# module_RF69.net
KiCad netlist of a schematic drawn in EAGLE
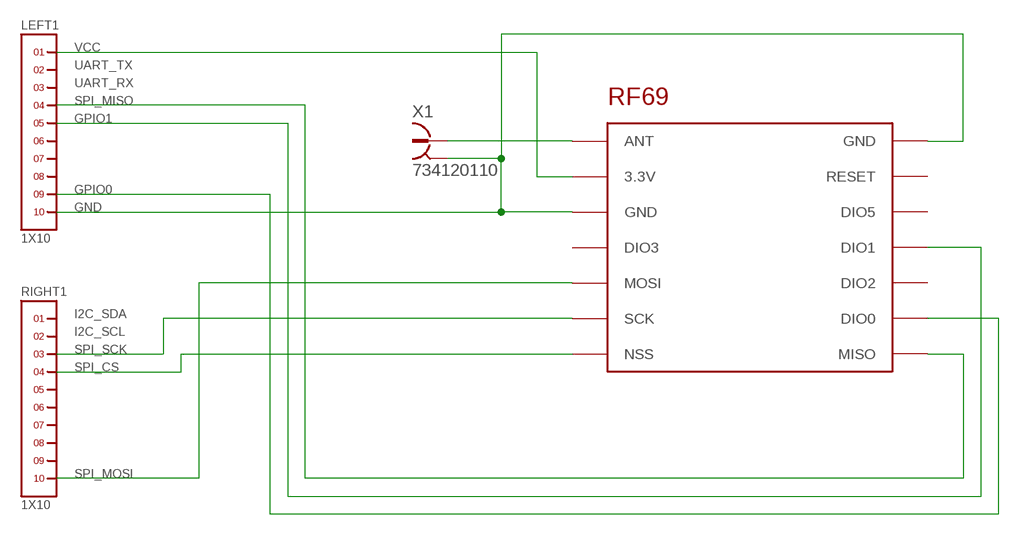
[diagram p0: schematic, sheet 1]

(export (version "E")
  (design (tool "Eeschema 10.0.6"))
  (components
    (comp (ref "LEFT1")
      (value "1X10")
      (footprint "eagle-import:1X10")
      (libsource (lib "eagle-import") (part "1X10"))
    )
    (comp (ref "RIGHT1")
      (value "1X10")
      (footprint "eagle-import:1X10")
      (libsource (lib "eagle-import") (part "1X10"))
    )
    (comp (ref "U$1")
      (value "RF69")
      (footprint "eagle-import:RF69")
      (libsource (lib "eagle-import") (part "RF69"))
    )
    (comp (ref "X1")
      (value "734120110")
      (footprint "eagle-import:734120110")
      (libsource (lib "eagle-import") (part "734120110"))
    )
  )
  (nets
    (net (code "1") (name "Net-(LEFT1-Pad1)") (class "Default")
      (node (ref "LEFT1") (pin "1") (pinfunction "1_1") (pintype "bidirectional"))
      (node (ref "U$1") (pin "3.3V") (pinfunction "3.3V_3.3V") (pintype "bidirectional"))
    )
    (net (code "2") (name "Net-(LEFT1-Pad4)") (class "Default")
      (node (ref "LEFT1") (pin "4") (pinfunction "4_4") (pintype "bidirectional"))
      (node (ref "U$1") (pin "MISO") (pinfunction "MISO_MISO") (pintype "bidirectional"))
    )
    (net (code "3") (name "Net-(LEFT1-Pad5)") (class "Default")
      (node (ref "LEFT1") (pin "5") (pinfunction "5_5") (pintype "bidirectional"))
      (node (ref "U$1") (pin "DIO1") (pinfunction "DIO1_DIO1") (pintype "bidirectional"))
    )
    (net (code "4") (name "Net-(LEFT1-Pad9)") (class "Default")
      (node (ref "LEFT1") (pin "9") (pinfunction "9_9") (pintype "bidirectional"))
      (node (ref "U$1") (pin "DIO0") (pinfunction "DIO0_DIO0") (pintype "bidirectional"))
    )
    (net (code "5") (name "Net-(LEFT1-Pad10)") (class "Default")
      (node (ref "LEFT1") (pin "10") (pinfunction "10_10") (pintype "bidirectional"))
      (node (ref "U$1") (pin "GND@1") (pinfunction "GND_GND@1") (pintype "bidirectional"))
      (node (ref "U$1") (pin "GND@2") (pinfunction "GND_GND@2") (pintype "bidirectional"))
      (node (ref "X1") (pin "S@1") (pinfunction "2_S@1") (pintype "passive"))
      (node (ref "X1") (pin "S@2") (pinfunction "2_S@2") (pintype "passive"))
      (node (ref "X1") (pin "S@3") (pinfunction "2_S@3") (pintype "passive"))
    )
    (net (code "6") (name "Net-(RIGHT1-Pad3)") (class "Default")
      (node (ref "RIGHT1") (pin "3") (pinfunction "3_3") (pintype "bidirectional"))
      (node (ref "U$1") (pin "SCK") (pinfunction "SCK_SCK") (pintype "bidirectional"))
    )
    (net (code "7") (name "Net-(RIGHT1-Pad4)") (class "Default")
      (node (ref "RIGHT1") (pin "4") (pinfunction "4_4") (pintype "bidirectional"))
      (node (ref "U$1") (pin "NSS") (pinfunction "NSS_NSS") (pintype "bidirectional"))
    )
    (net (code "8") (name "Net-(RIGHT1-Pad10)") (class "Default")
      (node (ref "RIGHT1") (pin "10") (pinfunction "10_10") (pintype "bidirectional"))
      (node (ref "U$1") (pin "MOSI") (pinfunction "MOSI_MOSI") (pintype "bidirectional"))
    )
    (net (code "9") (name "Net-(U$1-PadANT)") (class "Default")
      (node (ref "U$1") (pin "ANT") (pinfunction "ANT_ANT") (pintype "bidirectional"))
      (node (ref "X1") (pin "1") (pinfunction "1_1") (pintype "passive"))
    )
    (net (code "10") (name "unconnected-(LEFT1-Pad2)") (class "Default")
      (node (ref "LEFT1") (pin "2") (pinfunction "2_2") (pintype "bidirectional"))
    )
    (net (code "11") (name "unconnected-(LEFT1-Pad3)") (class "Default")
      (node (ref "LEFT1") (pin "3") (pinfunction "3_3") (pintype "bidirectional"))
    )
    (net (code "12") (name "unconnected-(LEFT1-Pad6)") (class "Default")
      (node (ref "LEFT1") (pin "6") (pinfunction "6_6") (pintype "bidirectional"))
    )
    (net (code "13") (name "unconnected-(LEFT1-Pad7)") (class "Default")
      (node (ref "LEFT1") (pin "7") (pinfunction "7_7") (pintype "bidirectional"))
    )
    (net (code "14") (name "unconnected-(LEFT1-Pad8)") (class "Default")
      (node (ref "LEFT1") (pin "8") (pinfunction "8_8") (pintype "bidirectional"))
    )
    (net (code "15") (name "unconnected-(RIGHT1-Pad1)") (class "Default")
      (node (ref "RIGHT1") (pin "1") (pinfunction "1_1") (pintype "bidirectional"))
    )
    (net (code "16") (name "unconnected-(RIGHT1-Pad2)") (class "Default")
      (node (ref "RIGHT1") (pin "2") (pinfunction "2_2") (pintype "bidirectional"))
    )
    (net (code "17") (name "unconnected-(RIGHT1-Pad5)") (class "Default")
      (node (ref "RIGHT1") (pin "5") (pinfunction "5_5") (pintype "bidirectional"))
    )
    (net (code "18") (name "unconnected-(RIGHT1-Pad6)") (class "Default")
      (node (ref "RIGHT1") (pin "6") (pinfunction "6_6") (pintype "bidirectional"))
    )
    (net (code "19") (name "unconnected-(RIGHT1-Pad7)") (class "Default")
      (node (ref "RIGHT1") (pin "7") (pinfunction "7_7") (pintype "bidirectional"))
    )
    (net (code "20") (name "unconnected-(RIGHT1-Pad8)") (class "Default")
      (node (ref "RIGHT1") (pin "8") (pinfunction "8_8") (pintype "bidirectional"))
    )
    (net (code "21") (name "unconnected-(RIGHT1-Pad9)") (class "Default")
      (node (ref "RIGHT1") (pin "9") (pinfunction "9_9") (pintype "bidirectional"))
    )
    (net (code "22") (name "unconnected-(U$1-PadDIO2)") (class "Default")
      (node (ref "U$1") (pin "DIO2") (pinfunction "DIO2_DIO2") (pintype "bidirectional"))
    )
    (net (code "23") (name "unconnected-(U$1-PadDIO3)") (class "Default")
      (node (ref "U$1") (pin "DIO3") (pinfunction "DIO3_DIO3") (pintype "bidirectional"))
    )
    (net (code "24") (name "unconnected-(U$1-PadDIO5)") (class "Default")
      (node (ref "U$1") (pin "DIO5") (pinfunction "DIO5_DIO5") (pintype "bidirectional"))
    )
    (net (code "25") (name "unconnected-(U$1-PadRESET)") (class "Default")
      (node (ref "U$1") (pin "RESET") (pinfunction "RESET_RESET") (pintype "bidirectional"))
    )
  )
)
